# rf.net
KiCad netlist of a schematic drawn in EAGLE
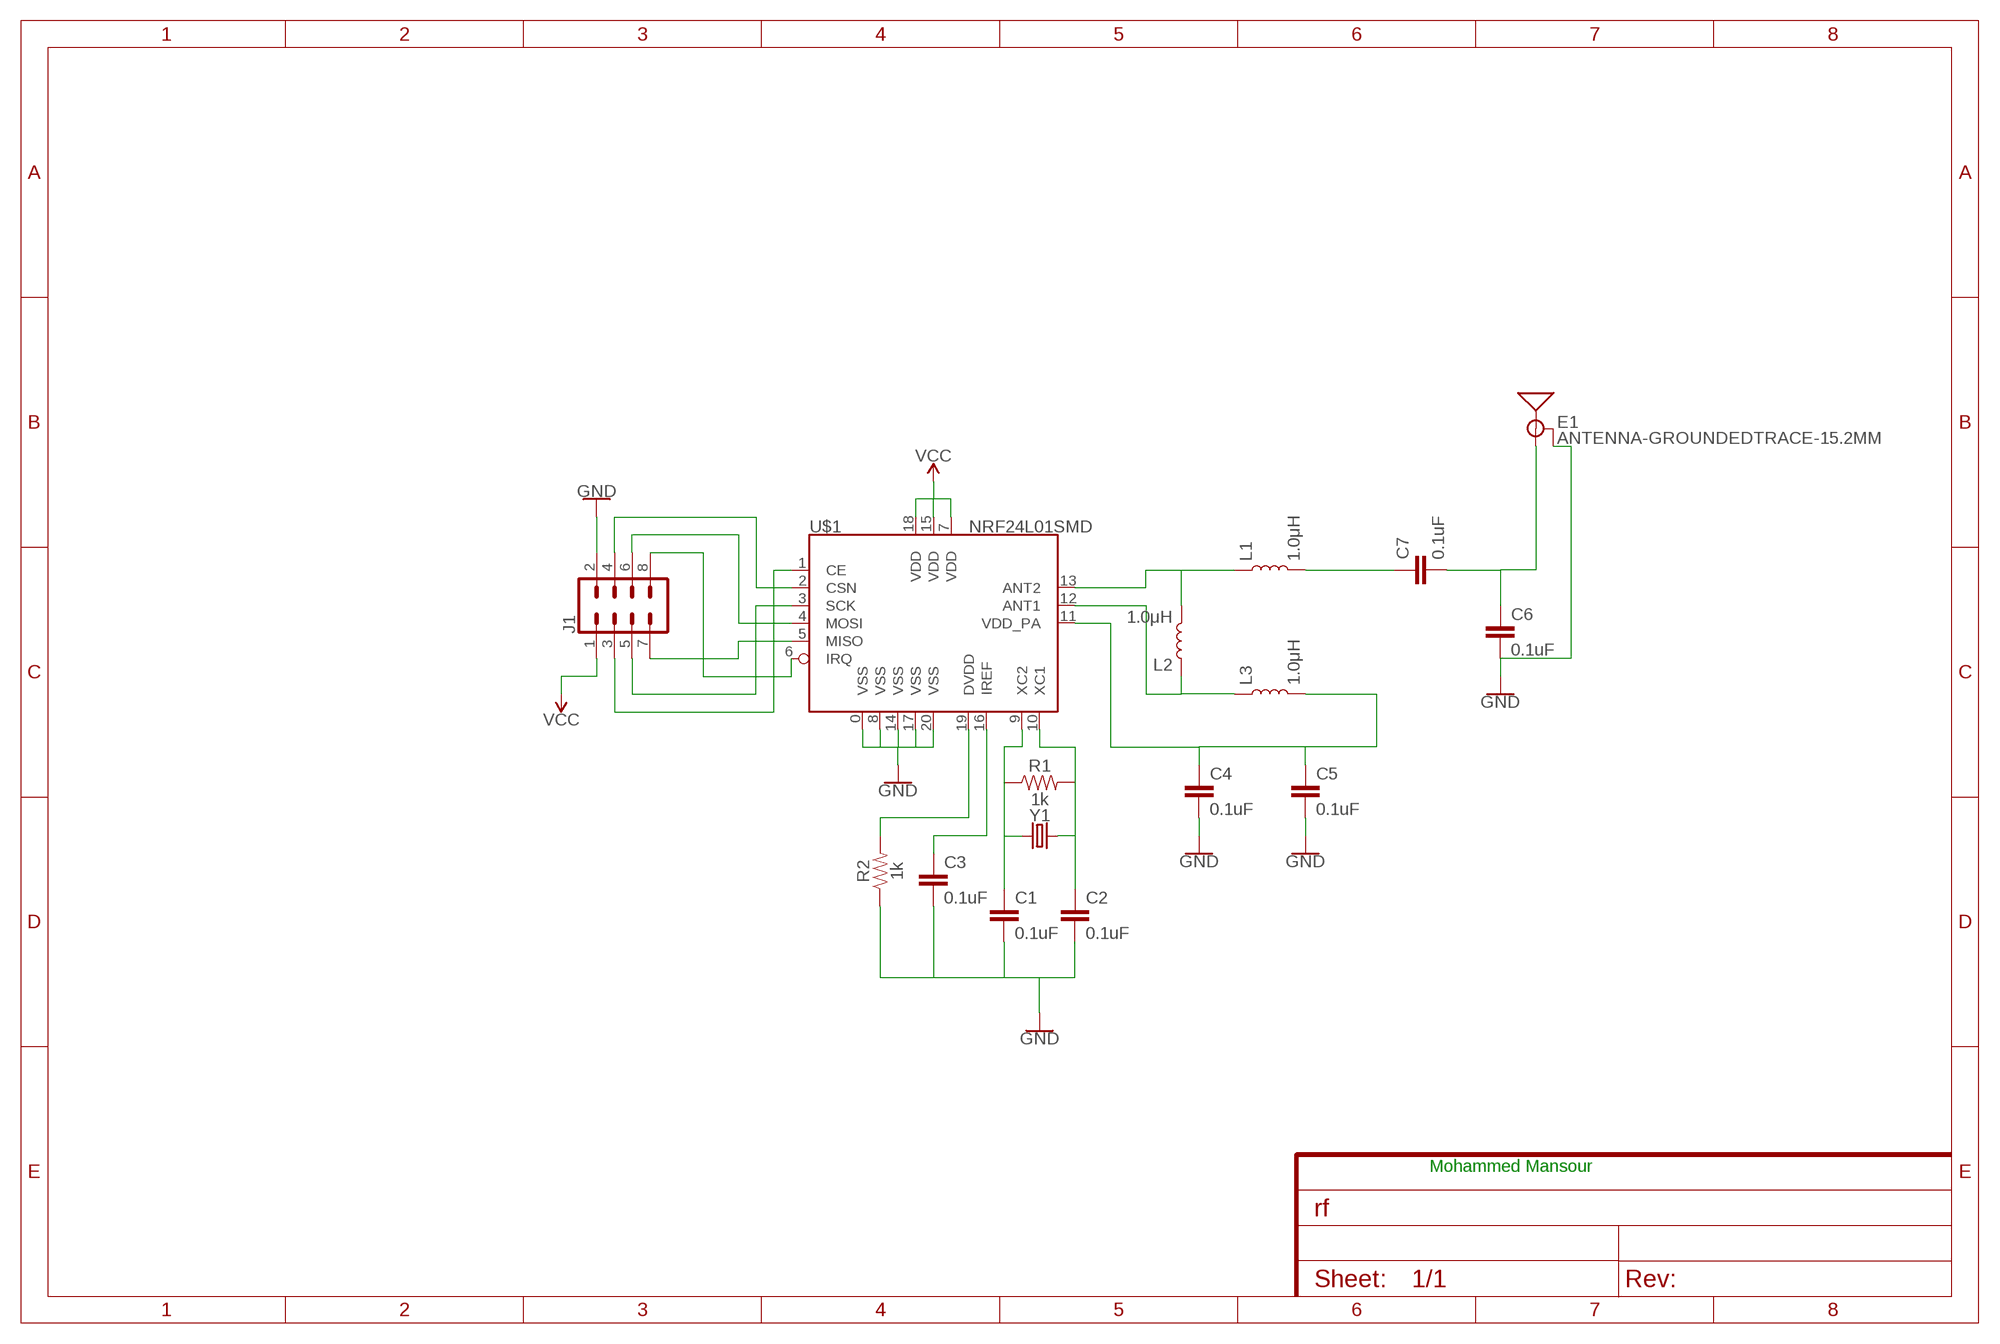
[diagram p0: schematic, sheet 1]

(export (version "E")
  (design (tool "Eeschema 10.0.6"))
  (components
    (comp (ref "C1")
      (value "0.1uF")
      (footprint "eagle-import:0402-TIGHT")
      (libsource (lib "eagle-import") (part "0.1UF-0402T-6.3V-10%-X7R"))
    )
    (comp (ref "C2")
      (value "0.1uF")
      (footprint "eagle-import:0402-TIGHT")
      (libsource (lib "eagle-import") (part "0.1UF-0402T-6.3V-10%-X7R"))
    )
    (comp (ref "C3")
      (value "0.1uF")
      (footprint "eagle-import:0402-TIGHT")
      (libsource (lib "eagle-import") (part "0.1UF-0402T-6.3V-10%-X7R"))
    )
    (comp (ref "C4")
      (value "0.1uF")
      (footprint "eagle-import:0402-TIGHT")
      (libsource (lib "eagle-import") (part "0.1UF-0402T-6.3V-10%-X7R"))
    )
    (comp (ref "C5")
      (value "0.1uF")
      (footprint "eagle-import:0402-TIGHT")
      (libsource (lib "eagle-import") (part "0.1UF-0402T-6.3V-10%-X7R"))
    )
    (comp (ref "C6")
      (value "0.1uF")
      (footprint "eagle-import:0402-TIGHT")
      (libsource (lib "eagle-import") (part "0.1UF-0402T-6.3V-10%-X7R"))
    )
    (comp (ref "C7")
      (value "0.1uF")
      (footprint "eagle-import:0402-TIGHT")
      (libsource (lib "eagle-import") (part "0.1UF-0402T-6.3V-10%-X7R"))
    )
    (comp (ref "E1")
      (value "ANTENNA-GROUNDEDTRACE-15.2MM")
      (footprint "eagle-import:TRACE_ANTENNA_2.4GHZ_15.2MM")
      (libsource (lib "eagle-import") (part "ANTENNA-GROUNDEDTRACE-15.2MM"))
    )
    (comp (ref "J1")
      (value "CONN_04X2")
      (footprint "eagle-import:2X4")
      (libsource (lib "eagle-import") (part "CONN_04X2"))
    )
    (comp (ref "L1")
      (value "1.0μH")
      (footprint "eagle-import:0805-WIDE")
      (libsource (lib "eagle-import") (part "1.0μH-0805_WIDE-1.0μH-1.4A-0.07OHM-1.4MM_H"))
    )
    (comp (ref "L2")
      (value "1.0μH")
      (footprint "eagle-import:0805-WIDE")
      (libsource (lib "eagle-import") (part "1.0μH-0805_WIDE-1.0μH-1.4A-0.07OHM-1.4MM_H"))
    )
    (comp (ref "L3")
      (value "1.0μH")
      (footprint "eagle-import:0805-WIDE")
      (libsource (lib "eagle-import") (part "1.0μH-0805_WIDE-1.0μH-1.4A-0.07OHM-1.4MM_H"))
    )
    (comp (ref "R1")
      (value "1k")
      (footprint "eagle-import:0402-TIGHT")
      (libsource (lib "eagle-import") (part "1KOHM-0402T-1/16W-1%"))
    )
    (comp (ref "R2")
      (value "1k")
      (footprint "eagle-import:0402-TIGHT")
      (libsource (lib "eagle-import") (part "1KOHM-0402T-1/16W-1%"))
    )
    (comp (ref "U$1")
      (value "NRF24L01SMD")
      (footprint "eagle-import:QFN20-4X4MM")
      (libsource (lib "eagle-import") (part "NRF24L01SMD"))
    )
    (comp (ref "Y1")
      (value "CRYSTALSMD-3.2X1.5")
      (footprint "eagle-import:CRYSTAL-SMD-3.2X1.5MM")
      (libsource (lib "eagle-import") (part "CRYSTALSMD-3.2X1.5"))
    )
  )
  (nets
    (net (code "1") (name "GND") (class "Default")
      (node (ref "C1") (pin "2") (pinfunction "2_2") (pintype "passive"))
      (node (ref "C2") (pin "2") (pinfunction "2_2") (pintype "passive"))
      (node (ref "C3") (pin "2") (pinfunction "2_2") (pintype "passive"))
      (node (ref "C4") (pin "2") (pinfunction "2_2") (pintype "passive"))
      (node (ref "C5") (pin "2") (pinfunction "2_2") (pintype "passive"))
      (node (ref "C6") (pin "2") (pinfunction "2_2") (pintype "passive"))
      (node (ref "E1") (pin "GND") (pinfunction "GND_GND") (pintype "bidirectional"))
      (node (ref "J1") (pin "2") (pinfunction "2_2") (pintype "passive"))
      (node (ref "R2") (pin "1") (pinfunction "1_1") (pintype "passive"))
      (node (ref "U$1") (pin "0") (pinfunction "VSS_0") (pintype "power_in"))
      (node (ref "U$1") (pin "14") (pinfunction "VSS_14") (pintype "power_in"))
      (node (ref "U$1") (pin "17") (pinfunction "VSS_17") (pintype "power_in"))
      (node (ref "U$1") (pin "20") (pinfunction "VSS_20") (pintype "power_in"))
      (node (ref "U$1") (pin "8") (pinfunction "VSS_8") (pintype "power_in"))
    )
    (net (code "2") (name "Net-(C7-Pad1)") (class "Default")
      (node (ref "C7") (pin "1") (pinfunction "1_1") (pintype "passive"))
      (node (ref "L1") (pin "2") (pinfunction "2_2") (pintype "passive"))
    )
    (net (code "3") (name "Net-(E1-SIGNAL)") (class "Default")
      (node (ref "C6") (pin "1") (pinfunction "1_1") (pintype "passive"))
      (node (ref "C7") (pin "2") (pinfunction "2_2") (pintype "passive"))
      (node (ref "E1") (pin "ANT") (pinfunction "SIGNAL_ANT") (pintype "bidirectional"))
    )
    (net (code "4") (name "Net-(U$1-ANT1)") (class "Default")
      (node (ref "L2") (pin "1") (pinfunction "1_1") (pintype "passive"))
      (node (ref "L3") (pin "1") (pinfunction "1_1") (pintype "passive"))
      (node (ref "U$1") (pin "12") (pinfunction "ANT1_12") (pintype "output"))
    )
    (net (code "5") (name "Net-(U$1-ANT2)") (class "Default")
      (node (ref "L1") (pin "1") (pinfunction "1_1") (pintype "passive"))
      (node (ref "L2") (pin "2") (pinfunction "2_2") (pintype "passive"))
      (node (ref "U$1") (pin "13") (pinfunction "ANT2_13") (pintype "output"))
    )
    (net (code "6") (name "Net-(U$1-CE)") (class "Default")
      (node (ref "J1") (pin "3") (pinfunction "3_3") (pintype "passive"))
      (node (ref "U$1") (pin "1") (pinfunction "CE_1") (pintype "input"))
    )
    (net (code "7") (name "Net-(U$1-CSN)") (class "Default")
      (node (ref "J1") (pin "4") (pinfunction "4_4") (pintype "passive"))
      (node (ref "U$1") (pin "2") (pinfunction "CSN_2") (pintype "input"))
    )
    (net (code "8") (name "Net-(U$1-DVDD)") (class "Default")
      (node (ref "R2") (pin "2") (pinfunction "2_2") (pintype "passive"))
      (node (ref "U$1") (pin "19") (pinfunction "DVDD_19") (pintype "power_in"))
    )
    (net (code "9") (name "Net-(U$1-IREF)") (class "Default")
      (node (ref "C3") (pin "1") (pinfunction "1_1") (pintype "passive"))
      (node (ref "U$1") (pin "16") (pinfunction "IREF_16") (pintype "input"))
    )
    (net (code "10") (name "Net-(U$1-IRQ)") (class "Default")
      (node (ref "J1") (pin "8") (pinfunction "8_8") (pintype "passive"))
      (node (ref "U$1") (pin "6") (pinfunction "IRQ_6") (pintype "output"))
    )
    (net (code "11") (name "Net-(U$1-MISO)") (class "Default")
      (node (ref "J1") (pin "7") (pinfunction "7_7") (pintype "passive"))
      (node (ref "U$1") (pin "5") (pinfunction "MISO_5") (pintype "output"))
    )
    (net (code "12") (name "Net-(U$1-MOSI)") (class "Default")
      (node (ref "J1") (pin "6") (pinfunction "6_6") (pintype "passive"))
      (node (ref "U$1") (pin "4") (pinfunction "MOSI_4") (pintype "input"))
    )
    (net (code "13") (name "Net-(U$1-SCK)") (class "Default")
      (node (ref "J1") (pin "5") (pinfunction "5_5") (pintype "passive"))
      (node (ref "U$1") (pin "3") (pinfunction "SCK_3") (pintype "input"))
    )
    (net (code "14") (name "Net-(U$1-VDD_PA)") (class "Default")
      (node (ref "C4") (pin "1") (pinfunction "1_1") (pintype "passive"))
      (node (ref "C5") (pin "1") (pinfunction "1_1") (pintype "passive"))
      (node (ref "L3") (pin "2") (pinfunction "2_2") (pintype "passive"))
      (node (ref "U$1") (pin "11") (pinfunction "VDD_PA_11") (pintype "power_in"))
    )
    (net (code "15") (name "Net-(U$1-XC1)") (class "Default")
      (node (ref "C2") (pin "1") (pinfunction "1_1") (pintype "passive"))
      (node (ref "R1") (pin "2") (pinfunction "2_2") (pintype "passive"))
      (node (ref "U$1") (pin "10") (pinfunction "XC1_10") (pintype "input"))
      (node (ref "Y1") (pin "P$2") (pinfunction "2_P$2") (pintype "passive"))
    )
    (net (code "16") (name "Net-(U$1-XC2)") (class "Default")
      (node (ref "C1") (pin "1") (pinfunction "1_1") (pintype "passive"))
      (node (ref "R1") (pin "1") (pinfunction "1_1") (pintype "passive"))
      (node (ref "U$1") (pin "9") (pinfunction "XC2_9") (pintype "input"))
      (node (ref "Y1") (pin "P$1") (pinfunction "1_P$1") (pintype "passive"))
    )
    (net (code "17") (name "VCC") (class "Default")
      (node (ref "J1") (pin "1") (pinfunction "1_1") (pintype "passive"))
      (node (ref "U$1") (pin "15") (pinfunction "VDD_15") (pintype "power_in"))
      (node (ref "U$1") (pin "18") (pinfunction "VDD_18") (pintype "power_in"))
      (node (ref "U$1") (pin "7") (pinfunction "VDD_7") (pintype "power_in"))
    )
  )
)
